# NRF24L01-RevB.net
KiCad netlist of a schematic drawn in EAGLE
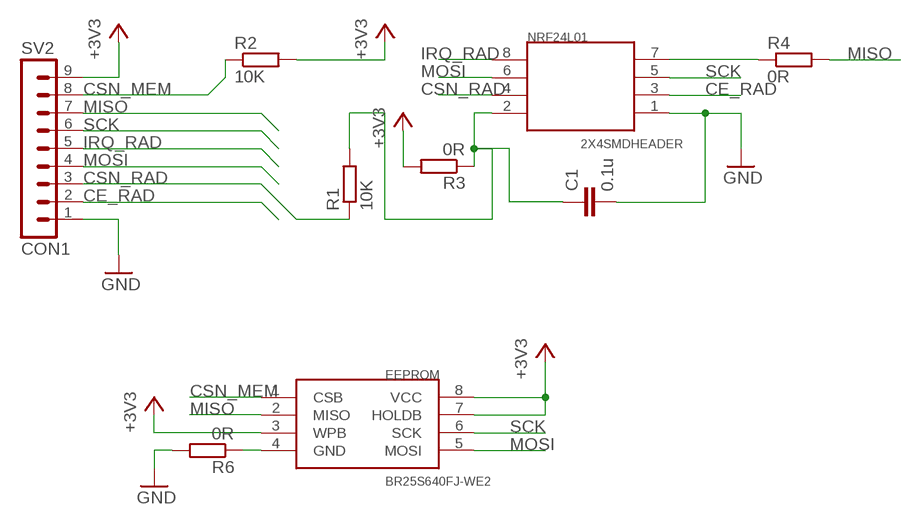
[diagram p0: schematic, sheet 1]

(export (version "E")
  (design (tool "Eeschema 10.0.6"))
  (components
    (comp (ref "C1")
      (value "0.1u")
      (footprint "eagle-import:C1206K")
      (libsource (lib "eagle-import") (part "C-EUC1206K"))
    )
    (comp (ref "EEPROM")
      (value "BR25S640FJ-WE2")
      (footprint "eagle-import:SO8")
      (libsource (lib "eagle-import") (part "BR25S640FJ-WE2"))
    )
    (comp (ref "NRF24L01")
      (value "2X4SMDHEADER")
      (footprint "eagle-import:TSM-110-XX-XXX-DV")
      (libsource (lib "eagle-import") (part "2X4SMDHEADER"))
    )
    (comp (ref "R1")
      (value "10K")
      (footprint "eagle-import:R1206")
      (libsource (lib "eagle-import") (part "R-EU_R1206"))
    )
    (comp (ref "R2")
      (value "10K")
      (footprint "eagle-import:R1206")
      (libsource (lib "eagle-import") (part "R-EU_R1206"))
    )
    (comp (ref "R3")
      (value "0R")
      (footprint "eagle-import:R1206")
      (libsource (lib "eagle-import") (part "R-EU_R1206"))
    )
    (comp (ref "R4")
      (value "0R")
      (footprint "eagle-import:R1206")
      (libsource (lib "eagle-import") (part "R-EU_R1206"))
    )
    (comp (ref "R6")
      (value "0R")
      (footprint "eagle-import:R1206")
      (libsource (lib "eagle-import") (part "R-EU_R1206"))
    )
    (comp (ref "SV2")
      (value "CON1")
      (footprint "eagle-import:MA09-1W")
      (libsource (lib "eagle-import") (part "MA09-1W"))
    )
  )
  (nets
    (net (code "1") (name "+3V3") (class "Default")
      (node (ref "EEPROM") (pin "3") (pinfunction "WPB_3") (pintype "bidirectional"))
      (node (ref "EEPROM") (pin "7") (pinfunction "HOLDB_7") (pintype "bidirectional"))
      (node (ref "EEPROM") (pin "8") (pinfunction "VCC_8") (pintype "bidirectional"))
      (node (ref "R2") (pin "2") (pinfunction "2_2") (pintype "passive"))
      (node (ref "R3") (pin "2") (pinfunction "2_2") (pintype "passive"))
      (node (ref "SV2") (pin "9") (pinfunction "9_9") (pintype "passive"))
    )
    (net (code "2") (name "/CE_RAD") (class "Default")
      (node (ref "NRF24L01") (pin "3") (pinfunction "3_3") (pintype "bidirectional"))
      (node (ref "SV2") (pin "2") (pinfunction "2_2") (pintype "passive"))
    )
    (net (code "3") (name "/CSN_MEM") (class "Default")
      (node (ref "EEPROM") (pin "1") (pinfunction "CSB_1") (pintype "bidirectional"))
      (node (ref "R2") (pin "1") (pinfunction "1_1") (pintype "passive"))
      (node (ref "SV2") (pin "8") (pinfunction "8_8") (pintype "passive"))
    )
    (net (code "4") (name "/CSN_RAD") (class "Default")
      (node (ref "NRF24L01") (pin "4") (pinfunction "4_4") (pintype "bidirectional"))
      (node (ref "R1") (pin "1") (pinfunction "1_1") (pintype "passive"))
      (node (ref "SV2") (pin "3") (pinfunction "3_3") (pintype "passive"))
    )
    (net (code "5") (name "/IRQ_RAD") (class "Default")
      (node (ref "NRF24L01") (pin "8") (pinfunction "8_8") (pintype "bidirectional"))
      (node (ref "SV2") (pin "5") (pinfunction "5_5") (pintype "passive"))
    )
    (net (code "6") (name "/MISO") (class "Default")
      (node (ref "EEPROM") (pin "2") (pinfunction "MISO_2") (pintype "bidirectional"))
      (node (ref "R4") (pin "2") (pinfunction "2_2") (pintype "passive"))
      (node (ref "SV2") (pin "7") (pinfunction "7_7") (pintype "passive"))
    )
    (net (code "7") (name "/MOSI") (class "Default")
      (node (ref "EEPROM") (pin "5") (pinfunction "MOSI_5") (pintype "bidirectional"))
      (node (ref "NRF24L01") (pin "6") (pinfunction "6_6") (pintype "bidirectional"))
      (node (ref "SV2") (pin "4") (pinfunction "4_4") (pintype "passive"))
    )
    (net (code "8") (name "/SCK") (class "Default")
      (node (ref "EEPROM") (pin "6") (pinfunction "SCK_6") (pintype "bidirectional"))
      (node (ref "NRF24L01") (pin "5") (pinfunction "5_5") (pintype "bidirectional"))
      (node (ref "SV2") (pin "6") (pinfunction "6_6") (pintype "passive"))
    )
    (net (code "9") (name "GND") (class "Default")
      (node (ref "C1") (pin "2") (pinfunction "2_2") (pintype "passive"))
      (node (ref "NRF24L01") (pin "1") (pinfunction "1_1") (pintype "bidirectional"))
      (node (ref "R6") (pin "2") (pinfunction "2_2") (pintype "passive"))
      (node (ref "SV2") (pin "1") (pinfunction "1_1") (pintype "passive"))
    )
    (net (code "10") (name "Net-(C1-Pad1)") (class "Default")
      (node (ref "C1") (pin "1") (pinfunction "1_1") (pintype "passive"))
      (node (ref "NRF24L01") (pin "2") (pinfunction "2_2") (pintype "bidirectional"))
      (node (ref "R1") (pin "2") (pinfunction "2_2") (pintype "passive"))
      (node (ref "R3") (pin "1") (pinfunction "1_1") (pintype "passive"))
    )
    (net (code "11") (name "Net-(EEPROM-GND)") (class "Default")
      (node (ref "EEPROM") (pin "4") (pinfunction "GND_4") (pintype "bidirectional"))
      (node (ref "R6") (pin "1") (pinfunction "1_1") (pintype "passive"))
    )
    (net (code "12") (name "Net-(NRF24L01-Pad7)") (class "Default")
      (node (ref "NRF24L01") (pin "7") (pinfunction "7_7") (pintype "bidirectional"))
      (node (ref "R4") (pin "1") (pinfunction "1_1") (pintype "passive"))
    )
  )
)
